# m1k-filter-mod-d1.net
KiCad netlist of a schematic drawn in EAGLE
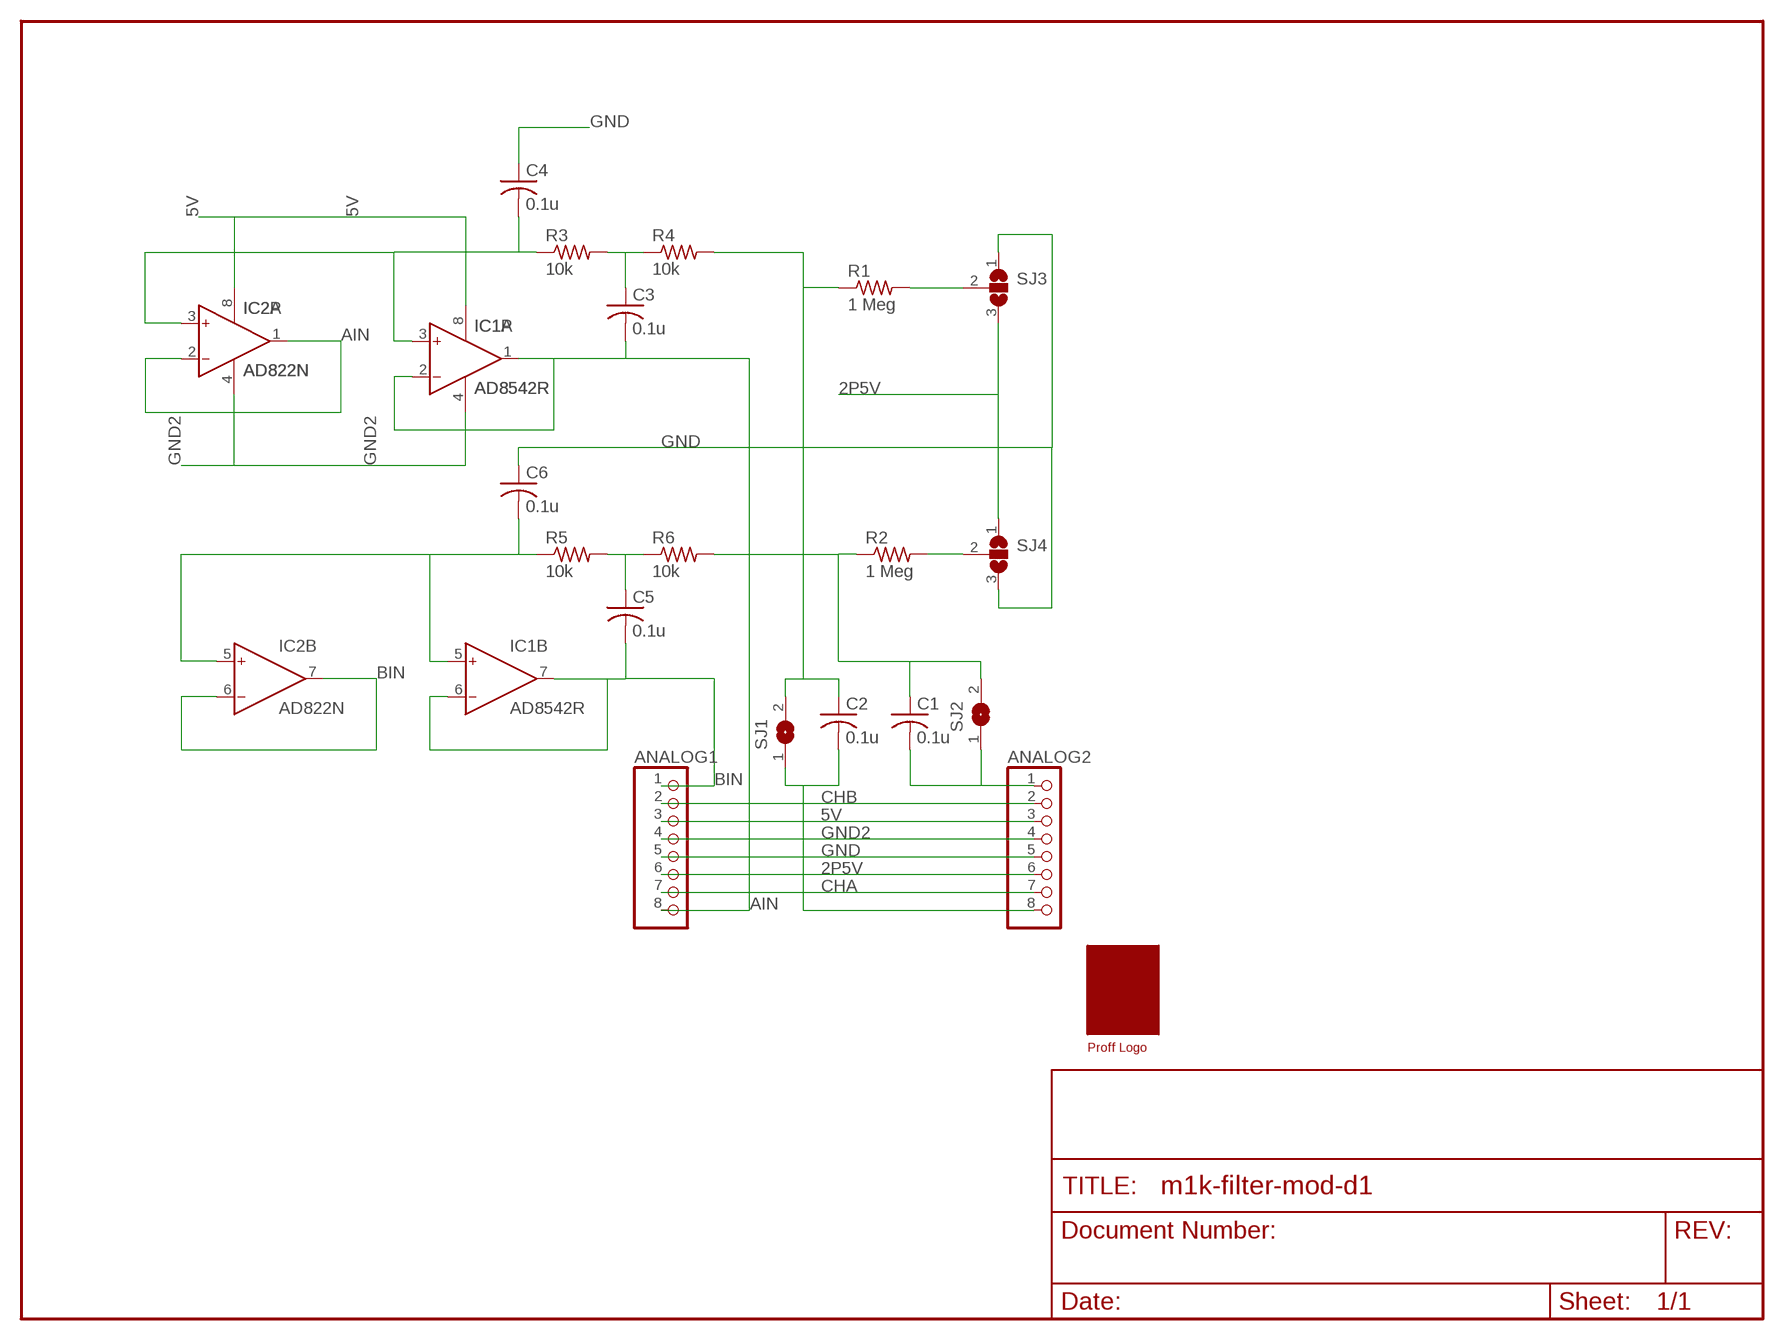
[diagram p0: schematic, sheet 1]

(export (version "E")
  (design (tool "Eeschema 10.0.6"))
  (components
    (comp (ref "ANALOG1")
      (value "PINHD-1X8")
      (footprint "eagle-import:1X08")
      (libsource (lib "eagle-import") (part "PINHD-1X8"))
    )
    (comp (ref "ANALOG2")
      (value "PINHD-1X8")
      (footprint "eagle-import:1X08")
      (libsource (lib "eagle-import") (part "PINHD-1X8"))
    )
    (comp (ref "C1")
      (value "0.1u")
      (footprint "eagle-import:C050-024X044")
      (libsource (lib "eagle-import") (part "C-US050-024X044"))
    )
    (comp (ref "C2")
      (value "0.1u")
      (footprint "eagle-import:C050-024X044")
      (libsource (lib "eagle-import") (part "C-US050-024X044"))
    )
    (comp (ref "C3")
      (value "0.1u")
      (footprint "eagle-import:C050-024X044")
      (libsource (lib "eagle-import") (part "C-US050-024X044"))
    )
    (comp (ref "C4")
      (value "0.1u")
      (footprint "eagle-import:C050-024X044")
      (libsource (lib "eagle-import") (part "C-US050-024X044"))
    )
    (comp (ref "C5")
      (value "0.1u")
      (footprint "eagle-import:C050-024X044")
      (libsource (lib "eagle-import") (part "C-US050-024X044"))
    )
    (comp (ref "C6")
      (value "0.1u")
      (footprint "eagle-import:C050-024X044")
      (libsource (lib "eagle-import") (part "C-US050-024X044"))
    )
    (comp (ref "IC1")
      (value "AD8542R")
      (footprint "eagle-import:SO8")
      (fields (field (name "MF") "ALTERA CORPORATION") (field (name "MPN") "AD8542ARZ-REEL"))
      (libsource (lib "eagle-import") (part "AD8542R"))
    )
    (comp (ref "IC2")
      (value "AD822N")
      (footprint "eagle-import:DIL08")
      (libsource (lib "eagle-import") (part "AD822N"))
    )
    (comp (ref "R1")
      (value "1 Meg")
      (footprint "eagle-import:0204_7")
      (libsource (lib "eagle-import") (part "R-US_0204/7"))
    )
    (comp (ref "R2")
      (value "1 Meg")
      (footprint "eagle-import:0204_7")
      (libsource (lib "eagle-import") (part "R-US_0204/7"))
    )
    (comp (ref "R3")
      (value "10k")
      (footprint "eagle-import:0204_7")
      (libsource (lib "eagle-import") (part "R-US_0204/7"))
    )
    (comp (ref "R4")
      (value "10k")
      (footprint "eagle-import:0204_7")
      (libsource (lib "eagle-import") (part "R-US_0204/7"))
    )
    (comp (ref "R5")
      (value "10k")
      (footprint "eagle-import:0204_7")
      (libsource (lib "eagle-import") (part "R-US_0204/7"))
    )
    (comp (ref "R6")
      (value "10k")
      (footprint "eagle-import:0204_7")
      (libsource (lib "eagle-import") (part "R-US_0204/7"))
    )
    (comp (ref "SJ1") (value "SJ") (footprint "eagle-import:SJ") (libsource (lib "eagle-import") (part "SJ")))
    (comp (ref "SJ2") (value "SJ") (footprint "eagle-import:SJ") (libsource (lib "eagle-import") (part "SJ")))
    (comp (ref "SJ3")
      (value "SJ2W")
      (footprint "eagle-import:SJ_2")
      (libsource (lib "eagle-import") (part "SJ2W"))
    )
    (comp (ref "SJ4")
      (value "SJ2W")
      (footprint "eagle-import:SJ_2")
      (libsource (lib "eagle-import") (part "SJ2W"))
    )
    (comp (ref "U$1")
      (value "PROFF")
      (footprint "eagle-import:PROFF")
      (libsource (lib "eagle-import") (part "PROFF"))
    )
  )
  (nets
    (net (code "1") (name "/2P5V") (class "Default")
      (node (ref "ANALOG1") (pin "6") (pinfunction "6_6") (pintype "passive"))
      (node (ref "ANALOG2") (pin "6") (pinfunction "6_6") (pintype "passive"))
      (node (ref "SJ3") (pin "3") (pinfunction "3_3") (pintype "passive"))
      (node (ref "SJ4") (pin "1") (pinfunction "1_1") (pintype "passive"))
    )
    (net (code "2") (name "/5V") (class "Default")
      (node (ref "ANALOG1") (pin "3") (pinfunction "3_3") (pintype "passive"))
      (node (ref "ANALOG2") (pin "3") (pinfunction "3_3") (pintype "passive"))
      (node (ref "IC1") (pin "8") (pinfunction "V+_8") (pintype "power_in"))
      (node (ref "IC2") (pin "8") (pinfunction "V+_8") (pintype "power_in"))
    )
    (net (code "3") (name "/AIN") (class "Default")
      (node (ref "ANALOG1") (pin "8") (pinfunction "8_8") (pintype "passive"))
      (node (ref "C3") (pin "2") (pinfunction "2_2") (pintype "passive"))
      (node (ref "IC1") (pin "1") (pinfunction "OUT_1") (pintype "output"))
      (node (ref "IC1") (pin "2") (pinfunction "IN-_2") (pintype "input"))
      (node (ref "IC2") (pin "1") (pinfunction "OUT_1") (pintype "output"))
      (node (ref "IC2") (pin "2") (pinfunction "IN-_2") (pintype "input"))
    )
    (net (code "4") (name "/BIN") (class "Default")
      (node (ref "ANALOG1") (pin "1") (pinfunction "1_1") (pintype "passive"))
      (node (ref "C5") (pin "2") (pinfunction "2_2") (pintype "passive"))
      (node (ref "IC1") (pin "6") (pinfunction "IN-_6") (pintype "input"))
      (node (ref "IC1") (pin "7") (pinfunction "OUT_7") (pintype "output"))
      (node (ref "IC2") (pin "6") (pinfunction "IN-_6") (pintype "input"))
      (node (ref "IC2") (pin "7") (pinfunction "OUT_7") (pintype "output"))
    )
    (net (code "5") (name "/CHA") (class "Default")
      (node (ref "ANALOG1") (pin "7") (pinfunction "7_7") (pintype "passive"))
      (node (ref "ANALOG2") (pin "7") (pinfunction "7_7") (pintype "passive"))
    )
    (net (code "6") (name "/CHB") (class "Default")
      (node (ref "ANALOG1") (pin "2") (pinfunction "2_2") (pintype "passive"))
      (node (ref "ANALOG2") (pin "2") (pinfunction "2_2") (pintype "passive"))
    )
    (net (code "7") (name "/GND") (class "Default")
      (node (ref "ANALOG1") (pin "5") (pinfunction "5_5") (pintype "passive"))
      (node (ref "ANALOG2") (pin "5") (pinfunction "5_5") (pintype "passive"))
      (node (ref "C4") (pin "1") (pinfunction "1_1") (pintype "passive"))
      (node (ref "C6") (pin "1") (pinfunction "1_1") (pintype "passive"))
      (node (ref "SJ3") (pin "1") (pinfunction "1_1") (pintype "passive"))
      (node (ref "SJ4") (pin "3") (pinfunction "3_3") (pintype "passive"))
    )
    (net (code "8") (name "/GND2") (class "Default")
      (node (ref "ANALOG1") (pin "4") (pinfunction "4_4") (pintype "passive"))
      (node (ref "ANALOG2") (pin "4") (pinfunction "4_4") (pintype "passive"))
      (node (ref "IC1") (pin "4") (pinfunction "V-_4") (pintype "power_in"))
      (node (ref "IC2") (pin "4") (pinfunction "V-_4") (pintype "power_in"))
    )
    (net (code "9") (name "Net-(ANALOG2-Pad1)") (class "Default")
      (node (ref "ANALOG2") (pin "1") (pinfunction "1_1") (pintype "passive"))
      (node (ref "C1") (pin "2") (pinfunction "2_2") (pintype "passive"))
      (node (ref "SJ2") (pin "1") (pinfunction "1_1") (pintype "passive"))
    )
    (net (code "10") (name "Net-(ANALOG2-Pad8)") (class "Default")
      (node (ref "ANALOG2") (pin "8") (pinfunction "8_8") (pintype "passive"))
      (node (ref "C2") (pin "2") (pinfunction "2_2") (pintype "passive"))
      (node (ref "SJ1") (pin "1") (pinfunction "1_1") (pintype "passive"))
    )
    (net (code "11") (name "Net-(C1-Pad1)") (class "Default")
      (node (ref "C1") (pin "1") (pinfunction "1_1") (pintype "passive"))
      (node (ref "R2") (pin "1") (pinfunction "1_1") (pintype "passive"))
      (node (ref "R6") (pin "2") (pinfunction "2_2") (pintype "passive"))
      (node (ref "SJ2") (pin "2") (pinfunction "2_2") (pintype "passive"))
    )
    (net (code "12") (name "Net-(C2-Pad1)") (class "Default")
      (node (ref "C2") (pin "1") (pinfunction "1_1") (pintype "passive"))
      (node (ref "R1") (pin "1") (pinfunction "1_1") (pintype "passive"))
      (node (ref "R4") (pin "2") (pinfunction "2_2") (pintype "passive"))
      (node (ref "SJ1") (pin "2") (pinfunction "2_2") (pintype "passive"))
    )
    (net (code "13") (name "Net-(C3-Pad1)") (class "Default")
      (node (ref "C3") (pin "1") (pinfunction "1_1") (pintype "passive"))
      (node (ref "R3") (pin "2") (pinfunction "2_2") (pintype "passive"))
      (node (ref "R4") (pin "1") (pinfunction "1_1") (pintype "passive"))
    )
    (net (code "14") (name "Net-(C5-Pad1)") (class "Default")
      (node (ref "C5") (pin "1") (pinfunction "1_1") (pintype "passive"))
      (node (ref "R5") (pin "2") (pinfunction "2_2") (pintype "passive"))
      (node (ref "R6") (pin "1") (pinfunction "1_1") (pintype "passive"))
    )
    (net (code "15") (name "Net-(IC1A-IN+)") (class "Default")
      (node (ref "C4") (pin "2") (pinfunction "2_2") (pintype "passive"))
      (node (ref "IC1") (pin "3") (pinfunction "IN+_3") (pintype "input"))
      (node (ref "IC2") (pin "3") (pinfunction "IN+_3") (pintype "input"))
      (node (ref "R3") (pin "1") (pinfunction "1_1") (pintype "passive"))
    )
    (net (code "16") (name "Net-(IC1B-IN+)") (class "Default")
      (node (ref "C6") (pin "2") (pinfunction "2_2") (pintype "passive"))
      (node (ref "IC1") (pin "5") (pinfunction "IN+_5") (pintype "input"))
      (node (ref "IC2") (pin "5") (pinfunction "IN+_5") (pintype "input"))
      (node (ref "R5") (pin "1") (pinfunction "1_1") (pintype "passive"))
    )
    (net (code "17") (name "Net-(R1-Pad2)") (class "Default")
      (node (ref "R1") (pin "2") (pinfunction "2_2") (pintype "passive"))
      (node (ref "SJ3") (pin "2") (pinfunction "2_2") (pintype "passive"))
    )
    (net (code "18") (name "Net-(R2-Pad2)") (class "Default")
      (node (ref "R2") (pin "2") (pinfunction "2_2") (pintype "passive"))
      (node (ref "SJ4") (pin "2") (pinfunction "2_2") (pintype "passive"))
    )
  )
)
